# FRA_daughter_v1.net
KiCad netlist of a schematic drawn in EAGLE
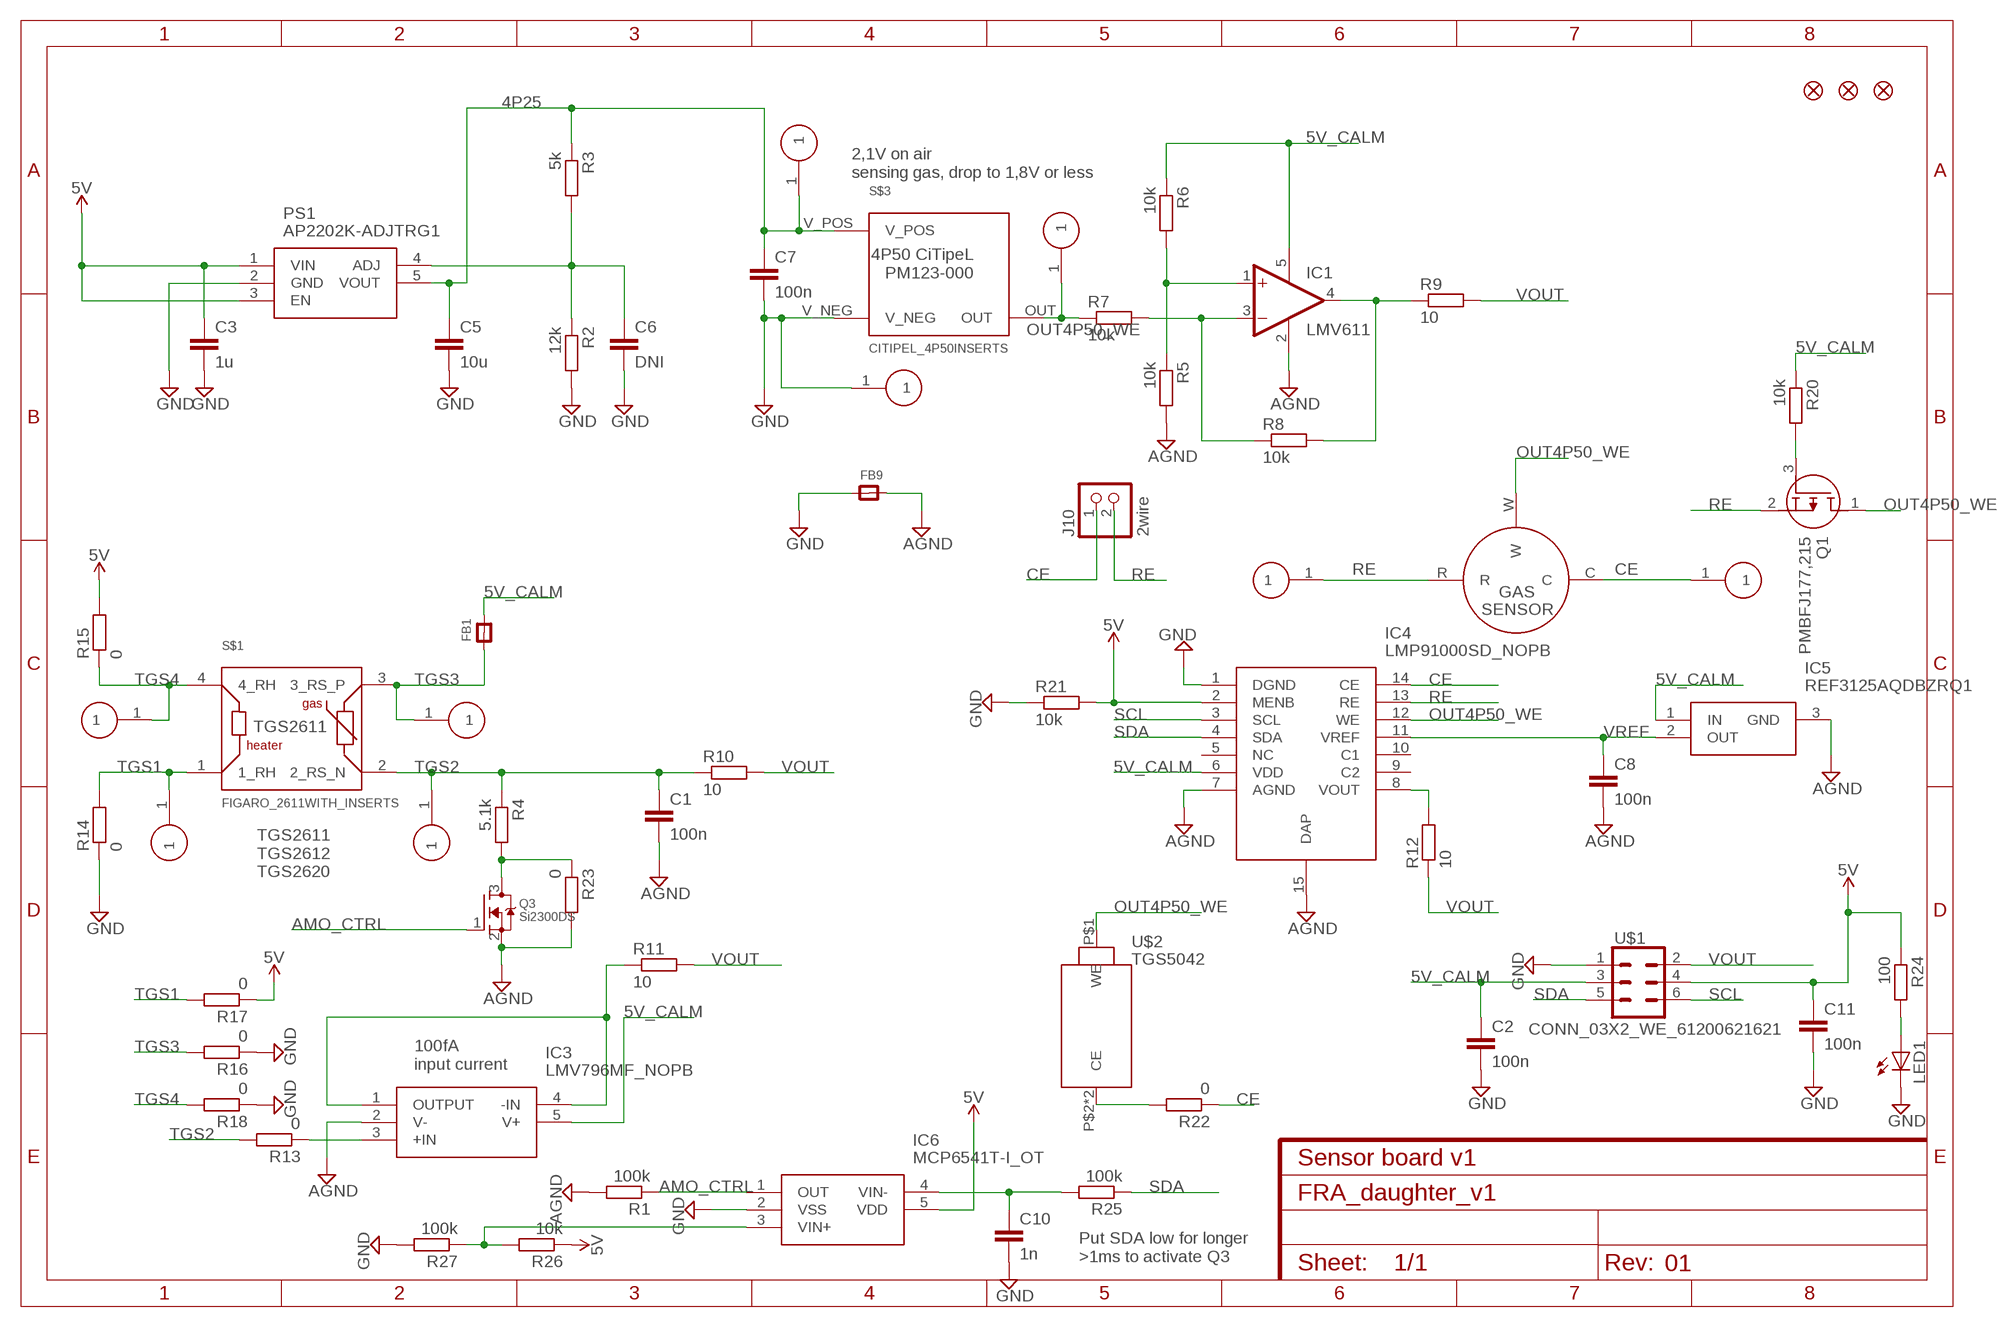
[diagram p0: schematic, sheet 1]

(export (version "E")
  (design (tool "Eeschema 10.0.6"))
  (components
    (comp (ref "C1")
      (value "100n")
      (footprint "eagle-import:C0603K")
      (libsource (lib "eagle-import") (part "C-EUC0603K"))
    )
    (comp (ref "C2")
      (value "100n")
      (footprint "eagle-import:C0603K")
      (libsource (lib "eagle-import") (part "C-EUC0603K"))
    )
    (comp (ref "C3")
      (value "1u")
      (footprint "eagle-import:C0603K")
      (libsource (lib "eagle-import") (part "C-EUC0603K"))
    )
    (comp (ref "C5")
      (value "10u")
      (footprint "eagle-import:C0603K")
      (libsource (lib "eagle-import") (part "C-EUC0603K"))
    )
    (comp (ref "C6")
      (value "DNI")
      (footprint "eagle-import:C0603K")
      (libsource (lib "eagle-import") (part "C-EUC0603K"))
    )
    (comp (ref "C7")
      (value "100n")
      (footprint "eagle-import:C0603K")
      (libsource (lib "eagle-import") (part "C-EUC0603K"))
    )
    (comp (ref "C8")
      (value "100n")
      (footprint "eagle-import:C0603K")
      (libsource (lib "eagle-import") (part "C-EUC0603K"))
    )
    (comp (ref "C10")
      (value "1n")
      (footprint "eagle-import:C0603K")
      (libsource (lib "eagle-import") (part "C-EUC0603K"))
    )
    (comp (ref "C11")
      (value "100n")
      (footprint "eagle-import:C0603K")
      (libsource (lib "eagle-import") (part "C-EUC0603K"))
    )
    (comp (ref "FB1")
      (value "FERRITE")
      (footprint "eagle-import:0603")
      (fields (field (name "PARTNO") "BLM18PG121SN1D"))
      (libsource (lib "eagle-import") (part "FERRITE"))
    )
    (comp (ref "FB9")
      (value "FERRITE")
      (footprint "eagle-import:0603")
      (fields (field (name "PARTNO") "BLM18PG121SN1D"))
      (libsource (lib "eagle-import") (part "FERRITE"))
    )
    (comp (ref "FID1")
      (value "FIDUCIAL\"\"")
      (footprint "eagle-import:FIDUCIAL_1MM")
      (libsource (lib "eagle-import") (part "FIDUCIAL{dblquote}{dblquote}"))
    )
    (comp (ref "FID2")
      (value "FIDUCIAL\"\"")
      (footprint "eagle-import:FIDUCIAL_1MM")
      (libsource (lib "eagle-import") (part "FIDUCIAL{dblquote}{dblquote}"))
    )
    (comp (ref "FID4")
      (value "FIDUCIAL\"\"")
      (footprint "eagle-import:FIDUCIAL_1MM")
      (libsource (lib "eagle-import") (part "FIDUCIAL{dblquote}{dblquote}"))
    )
    (comp (ref "IC1")
      (value "LMV611")
      (footprint "eagle-import:SC70-5L")
      (libsource (lib "eagle-import") (part "OPA333DCK"))
    )
    (comp (ref "IC3")
      (value "LMV796MF_NOPB")
      (footprint "eagle-import:SOT95P280X145-5N")
      (fields
        (field (name "MANUFACTURER_PART_NUMBER") "LMV796MF/NOPB")
        (field (name "MOUSER_PART_NUMBER") "926-LMV796MF/NOPB")
      )
      (libsource (lib "eagle-import") (part "LMV796MF_NOPB"))
    )
    (comp (ref "IC4")
      (value "LMP91000SD_NOPB")
      (footprint "eagle-import:SON50P400X400X80-15N")
      (fields
        (field (name "MANUFACTURER_PART_NUMBER") "LMP91000SD/NOPB")
        (field (name "MOUSER_PART_NUMBER") "926-LMP91000SD/NOPB")
      )
      (libsource (lib "eagle-import") (part "LMP91000SD_NOPB"))
    )
    (comp (ref "IC5")
      (value "REF3125AQDBZRQ1")
      (footprint "eagle-import:SOT95P237X112-3N")
      (fields (field (name "MOUSER_PART_NUMBER") "595-REF3125AQDBZRQ1"))
      (libsource (lib "eagle-import") (part "REF3125AQDBZRQ1"))
    )
    (comp (ref "IC6")
      (value "MCP6541T-I_OT")
      (footprint "eagle-import:SOT95P270X145-5N")
      (fields
        (field (name "MANUFACTURER_PART_NUMBER") "MCP6541T-I/OT")
        (field (name "MOUSER_PART_NUMBER") "579-MCP6541T-I/OT")
      )
      (libsource (lib "eagle-import") (part "MCP6541T-I_OT"))
    )
    (comp (ref "J1")
      (value "INSERT_MM5_06691.5MM")
      (footprint "eagle-import:INSERT_1MM5_9372")
      (libsource (lib "eagle-import") (part "INSERT_MM5_06691.5MM"))
    )
    (comp (ref "J2")
      (value "TGS3")
      (footprint "eagle-import:INSERT_MM5_0669")
      (libsource (lib "eagle-import") (part "INSERT_MM5_0669"))
    )
    (comp (ref "J3")
      (value "TGS2")
      (footprint "eagle-import:INSERT_MM5_0669")
      (libsource (lib "eagle-import") (part "INSERT_MM5_0669"))
    )
    (comp (ref "J4")
      (value "TGS1")
      (footprint "eagle-import:INSERT_MM5_0669")
      (libsource (lib "eagle-import") (part "INSERT_MM5_0669"))
    )
    (comp (ref "J5")
      (value "TGS4")
      (footprint "eagle-import:INSERT_MM5_0669")
      (libsource (lib "eagle-import") (part "INSERT_MM5_0669"))
    )
    (comp (ref "J6")
      (value "INSERT_MM5_06691.5MM")
      (footprint "eagle-import:INSERT_1MM5_9372")
      (libsource (lib "eagle-import") (part "INSERT_MM5_06691.5MM"))
    )
    (comp (ref "J7")
      (value "INSERT_MM5_06691.5MM")
      (footprint "eagle-import:INSERT_1MM5_9372")
      (libsource (lib "eagle-import") (part "INSERT_MM5_06691.5MM"))
    )
    (comp (ref "J8")
      (value "INSERT_MM5_06691.5MM")
      (footprint "eagle-import:INSERT_1MM5_9372")
      (libsource (lib "eagle-import") (part "INSERT_MM5_06691.5MM"))
    )
    (comp (ref "J9")
      (value "INSERT_MM5_06691.5MM")
      (footprint "eagle-import:INSERT_1MM5_9372")
      (libsource (lib "eagle-import") (part "INSERT_MM5_06691.5MM"))
    )
    (comp (ref "J10")
      (value "2wire")
      (footprint "eagle-import:1X02")
      (fields (field (name "PARTNO") "TSW-102-07-G-S"))
      (libsource (lib "eagle-import") (part "PINHD-1X2"))
    )
    (comp (ref "LED1")
      (value "LEDCHIP-LED0603")
      (footprint "eagle-import:CHIP-LED0603")
      (libsource (lib "eagle-import") (part "LEDCHIP-LED0603"))
    )
    (comp (ref "PS1")
      (value "AP2202K-ADJTRG1")
      (footprint "eagle-import:SOT95P280X145-5N")
      (fields (field (name "MOUSER_PART_NUMBER") "621-AP2202K-ADJTRG1"))
      (libsource (lib "eagle-import") (part "AP2202K-ADJTRG1"))
    )
    (comp (ref "Q1")
      (value "PMBFJ177,215")
      (footprint "eagle-import:SOT95P230X110-3N")
      (fields (field (name "MOUSER_PART_NUMBER") "771-PMBFJ177-T/R"))
      (libsource (lib "eagle-import") (part "PMBFJ177,215"))
    )
    (comp (ref "Q3")
      (value "Si2300DS")
      (footprint "eagle-import:SOT23")
      (libsource (lib "eagle-import") (part "MOSFET-NREFLOW"))
    )
    (comp (ref "R1")
      (value "100k")
      (footprint "eagle-import:R0603")
      (libsource (lib "eagle-import") (part "R-EU_R0603"))
    )
    (comp (ref "R2")
      (value "12k")
      (footprint "eagle-import:R0603")
      (libsource (lib "eagle-import") (part "R-EU_R0603"))
    )
    (comp (ref "R3")
      (value "5k")
      (footprint "eagle-import:R0603")
      (libsource (lib "eagle-import") (part "R-EU_R0603"))
    )
    (comp (ref "R4")
      (value "5.1k")
      (footprint "eagle-import:R0603")
      (libsource (lib "eagle-import") (part "R-EU_R0603"))
    )
    (comp (ref "R5")
      (value "10k")
      (footprint "eagle-import:R0603")
      (libsource (lib "eagle-import") (part "R-EU_R0603"))
    )
    (comp (ref "R6")
      (value "10k")
      (footprint "eagle-import:R0603")
      (libsource (lib "eagle-import") (part "R-EU_R0603"))
    )
    (comp (ref "R7")
      (value "10k")
      (footprint "eagle-import:R0603")
      (libsource (lib "eagle-import") (part "R-EU_R0603"))
    )
    (comp (ref "R8")
      (value "10k")
      (footprint "eagle-import:R0603")
      (libsource (lib "eagle-import") (part "R-EU_R0603"))
    )
    (comp (ref "R9")
      (value "10")
      (footprint "eagle-import:R0603")
      (libsource (lib "eagle-import") (part "R-EU_R0603"))
    )
    (comp (ref "R10")
      (value "10")
      (footprint "eagle-import:R0603")
      (libsource (lib "eagle-import") (part "R-EU_R0603"))
    )
    (comp (ref "R11")
      (value "10")
      (footprint "eagle-import:R0603")
      (libsource (lib "eagle-import") (part "R-EU_R0603"))
    )
    (comp (ref "R12")
      (value "10")
      (footprint "eagle-import:R0603")
      (libsource (lib "eagle-import") (part "R-EU_R0603"))
    )
    (comp (ref "R13")
      (value "0")
      (footprint "eagle-import:R0603")
      (libsource (lib "eagle-import") (part "R-EU_R0603"))
    )
    (comp (ref "R14")
      (value "0")
      (footprint "eagle-import:R0603")
      (libsource (lib "eagle-import") (part "R-EU_R0603"))
    )
    (comp (ref "R15")
      (value "0")
      (footprint "eagle-import:R0603")
      (libsource (lib "eagle-import") (part "R-EU_R0603"))
    )
    (comp (ref "R16")
      (value "0")
      (footprint "eagle-import:R0603")
      (libsource (lib "eagle-import") (part "R-EU_R0603"))
    )
    (comp (ref "R17")
      (value "0")
      (footprint "eagle-import:R0603")
      (libsource (lib "eagle-import") (part "R-EU_R0603"))
    )
    (comp (ref "R18")
      (value "0")
      (footprint "eagle-import:R0603")
      (libsource (lib "eagle-import") (part "R-EU_R0603"))
    )
    (comp (ref "R20")
      (value "10k")
      (footprint "eagle-import:R0603")
      (libsource (lib "eagle-import") (part "R-EU_R0603"))
    )
    (comp (ref "R21")
      (value "10k")
      (footprint "eagle-import:R0603")
      (libsource (lib "eagle-import") (part "R-EU_R0603"))
    )
    (comp (ref "R22")
      (value "0")
      (footprint "eagle-import:R0603")
      (libsource (lib "eagle-import") (part "R-EU_R0603"))
    )
    (comp (ref "R23")
      (value "0")
      (footprint "eagle-import:R0603")
      (libsource (lib "eagle-import") (part "R-EU_R0603"))
    )
    (comp (ref "R24")
      (value "100")
      (footprint "eagle-import:R0603")
      (libsource (lib "eagle-import") (part "R-EU_R0603"))
    )
    (comp (ref "R25")
      (value "100k")
      (footprint "eagle-import:R0603")
      (libsource (lib "eagle-import") (part "R-EU_R0603"))
    )
    (comp (ref "R26")
      (value "10k")
      (footprint "eagle-import:R0603")
      (libsource (lib "eagle-import") (part "R-EU_R0603"))
    )
    (comp (ref "R27")
      (value "100k")
      (footprint "eagle-import:R0603")
      (libsource (lib "eagle-import") (part "R-EU_R0603"))
    )
    (comp (ref "S$1")
      (value "FIGARO_2611WITH_INSERTS")
      (footprint "eagle-import:TH4_TGS2611_INSERTS")
      (libsource (lib "eagle-import") (part "FIGARO_2611WITH_INSERTS"))
    )
    (comp (ref "S$3")
      (value "CITIPEL_4P50INSERTS")
      (footprint "eagle-import:TH3_4P50_INSERTS")
      (libsource (lib "eagle-import") (part "CITIPEL_4P50INSERTS"))
    )
    (comp (ref "U$1")
      (value "CONN_03X2_WE_61200621621")
      (footprint "eagle-import:WE_61200621621")
      (libsource (lib "eagle-import") (part "CONN_03X2_WE_61200621621"))
    )
    (comp (ref "U$2")
      (value "TGS5042")
      (footprint "eagle-import:TGS5042")
      (libsource (lib "eagle-import") (part "TGS5042"))
    )
    (comp (ref "X1")
      (value "3-ELECTRODE-GAS-SENSORINS")
      (footprint "eagle-import:3-ELECTRODE_INSETRS")
      (libsource (lib "eagle-import") (part "3-ELECTRODE-GAS-SENSORINS"))
    )
  )
  (nets
    (net (code "1") (name "/4P25") (class "Default")
      (node (ref "C5") (pin "1") (pinfunction "1_1") (pintype "passive"))
      (node (ref "C7") (pin "1") (pinfunction "1_1") (pintype "passive"))
      (node (ref "J6") (pin "1") (pinfunction "1_1") (pintype "bidirectional"))
      (node (ref "PS1") (pin "5") (pinfunction "VOUT_5") (pintype "power_in"))
      (node (ref "R3") (pin "1") (pinfunction "1_1") (pintype "passive"))
      (node (ref "S$3") (pin "V_POS") (pinfunction "V_POS_V_POS") (pintype "power_in"))
    )
    (net (code "2") (name "/5V_CALM") (class "Default")
      (node (ref "C2") (pin "1") (pinfunction "1_1") (pintype "passive"))
      (node (ref "FB1") (pin "2") (pinfunction "P$2_2") (pintype "passive"))
      (node (ref "IC1") (pin "5") (pinfunction "V+_5") (pintype "power_in"))
      (node (ref "IC3") (pin "5") (pinfunction "V+_5") (pintype "bidirectional"))
      (node (ref "IC4") (pin "6") (pinfunction "VDD_6") (pintype "power_in"))
      (node (ref "IC5") (pin "1") (pinfunction "IN_1") (pintype "bidirectional"))
      (node (ref "R20") (pin "1") (pinfunction "1_1") (pintype "passive"))
      (node (ref "R6") (pin "1") (pinfunction "1_1") (pintype "passive"))
      (node (ref "U$1") (pin "3") (pinfunction "3_3") (pintype "bidirectional"))
    )
    (net (code "3") (name "/AMO_CTRL") (class "Default")
      (node (ref "IC6") (pin "1") (pinfunction "OUT_1") (pintype "output"))
      (node (ref "Q3") (pin "1") (pinfunction "G_1") (pintype "bidirectional"))
      (node (ref "R1") (pin "1") (pinfunction "1_1") (pintype "passive"))
    )
    (net (code "4") (name "/CE") (class "Default")
      (node (ref "IC4") (pin "14") (pinfunction "CE_14") (pintype "input"))
      (node (ref "J10") (pin "1") (pinfunction "1_1") (pintype "passive"))
      (node (ref "J9") (pin "1") (pinfunction "1_1") (pintype "bidirectional"))
      (node (ref "R22") (pin "1") (pinfunction "1_1") (pintype "passive"))
      (node (ref "X1") (pin "C") (pinfunction "C_C") (pintype "bidirectional"))
    )
    (net (code "5") (name "/OUT4P50_WE") (class "Default")
      (node (ref "IC4") (pin "12") (pinfunction "WE_12") (pintype "input"))
      (node (ref "J7") (pin "1") (pinfunction "1_1") (pintype "bidirectional"))
      (node (ref "Q1") (pin "1") (pinfunction "D_1") (pintype "bidirectional"))
      (node (ref "R7") (pin "1") (pinfunction "1_1") (pintype "passive"))
      (node (ref "S$3") (pin "OUT") (pinfunction "OUT_OUT") (pintype "bidirectional"))
      (node (ref "U$2") (pin "P$1") (pinfunction "WE_P$1") (pintype "bidirectional"))
      (node (ref "X1") (pin "W") (pinfunction "W_W") (pintype "bidirectional"))
    )
    (net (code "6") (name "/RE") (class "Default")
      (node (ref "IC4") (pin "13") (pinfunction "RE_13") (pintype "input"))
      (node (ref "J10") (pin "2") (pinfunction "2_2") (pintype "passive"))
      (node (ref "J8") (pin "1") (pinfunction "1_1") (pintype "bidirectional"))
      (node (ref "Q1") (pin "2") (pinfunction "S_2") (pintype "bidirectional"))
      (node (ref "X1") (pin "R") (pinfunction "R_R") (pintype "bidirectional"))
    )
    (net (code "7") (name "/SCL") (class "Default")
      (node (ref "IC4") (pin "3") (pinfunction "SCL_3") (pintype "input"))
      (node (ref "U$1") (pin "6") (pinfunction "6_6") (pintype "bidirectional"))
    )
    (net (code "8") (name "/SDA") (class "Default")
      (node (ref "IC4") (pin "4") (pinfunction "SDA_4") (pintype "bidirectional"))
      (node (ref "R25") (pin "1") (pinfunction "1_1") (pintype "passive"))
      (node (ref "U$1") (pin "5") (pinfunction "5_5") (pintype "bidirectional"))
    )
    (net (code "9") (name "/TGS1") (class "Default")
      (node (ref "J4") (pin "1") (pinfunction "1_1") (pintype "bidirectional"))
      (node (ref "R14") (pin "2") (pinfunction "2_2") (pintype "passive"))
      (node (ref "R17") (pin "2") (pinfunction "2_2") (pintype "passive"))
      (node (ref "S$1") (pin "1") (pinfunction "1_RH_1") (pintype "bidirectional"))
    )
    (net (code "10") (name "/TGS2") (class "Default")
      (node (ref "C1") (pin "1") (pinfunction "1_1") (pintype "passive"))
      (node (ref "J3") (pin "1") (pinfunction "1_1") (pintype "bidirectional"))
      (node (ref "R10") (pin "1") (pinfunction "1_1") (pintype "passive"))
      (node (ref "R13") (pin "2") (pinfunction "2_2") (pintype "passive"))
      (node (ref "R4") (pin "1") (pinfunction "1_1") (pintype "passive"))
      (node (ref "S$1") (pin "2") (pinfunction "2_RS_N_2") (pintype "bidirectional"))
    )
    (net (code "11") (name "/TGS3") (class "Default")
      (node (ref "FB1") (pin "1") (pinfunction "P$1_1") (pintype "passive"))
      (node (ref "J2") (pin "1") (pinfunction "1_1") (pintype "bidirectional"))
      (node (ref "R16") (pin "2") (pinfunction "2_2") (pintype "passive"))
      (node (ref "S$1") (pin "3") (pinfunction "3_RS_P_3") (pintype "bidirectional"))
    )
    (net (code "12") (name "/TGS4") (class "Default")
      (node (ref "J5") (pin "1") (pinfunction "1_1") (pintype "bidirectional"))
      (node (ref "R15") (pin "1") (pinfunction "1_1") (pintype "passive"))
      (node (ref "R18") (pin "2") (pinfunction "2_2") (pintype "passive"))
      (node (ref "S$1") (pin "4") (pinfunction "4_RH_4") (pintype "bidirectional"))
    )
    (net (code "13") (name "/VOUT") (class "Default")
      (node (ref "R10") (pin "2") (pinfunction "2_2") (pintype "passive"))
      (node (ref "R11") (pin "2") (pinfunction "2_2") (pintype "passive"))
      (node (ref "R12") (pin "1") (pinfunction "1_1") (pintype "passive"))
      (node (ref "R9") (pin "2") (pinfunction "2_2") (pintype "passive"))
      (node (ref "U$1") (pin "2") (pinfunction "2_2") (pintype "bidirectional"))
    )
    (net (code "14") (name "/VREF") (class "Default")
      (node (ref "C8") (pin "1") (pinfunction "1_1") (pintype "passive"))
      (node (ref "IC4") (pin "11") (pinfunction "VREF_11") (pintype "input"))
      (node (ref "IC5") (pin "2") (pinfunction "OUT_2") (pintype "bidirectional"))
    )
    (net (code "15") (name "5V") (class "Default")
      (node (ref "C11") (pin "1") (pinfunction "1_1") (pintype "passive"))
      (node (ref "C3") (pin "1") (pinfunction "1_1") (pintype "passive"))
      (node (ref "IC4") (pin "2") (pinfunction "MENB_2") (pintype "input"))
      (node (ref "IC6") (pin "5") (pinfunction "VDD_5") (pintype "power_in"))
      (node (ref "PS1") (pin "1") (pinfunction "VIN_1") (pintype "power_in"))
      (node (ref "PS1") (pin "3") (pinfunction "EN_3") (pintype "input"))
      (node (ref "R15") (pin "2") (pinfunction "2_2") (pintype "passive"))
      (node (ref "R17") (pin "1") (pinfunction "1_1") (pintype "passive"))
      (node (ref "R21") (pin "2") (pinfunction "2_2") (pintype "passive"))
      (node (ref "R24") (pin "1") (pinfunction "1_1") (pintype "passive"))
      (node (ref "R26") (pin "1") (pinfunction "1_1") (pintype "passive"))
      (node (ref "U$1") (pin "4") (pinfunction "4_4") (pintype "bidirectional"))
    )
    (net (code "16") (name "AGND") (class "Default")
      (node (ref "C1") (pin "2") (pinfunction "2_2") (pintype "passive"))
      (node (ref "C8") (pin "2") (pinfunction "2_2") (pintype "passive"))
      (node (ref "FB9") (pin "2") (pinfunction "P$2_2") (pintype "passive"))
      (node (ref "IC1") (pin "2") (pinfunction "V-_2") (pintype "power_in"))
      (node (ref "IC3") (pin "2") (pinfunction "V-_2") (pintype "bidirectional"))
      (node (ref "IC4") (pin "15") (pinfunction "DAP_15") (pintype "power_in"))
      (node (ref "IC4") (pin "7") (pinfunction "AGND_7") (pintype "power_in"))
      (node (ref "IC5") (pin "3") (pinfunction "GND_3") (pintype "bidirectional"))
      (node (ref "Q3") (pin "2") (pinfunction "S_2") (pintype "bidirectional"))
      (node (ref "R1") (pin "2") (pinfunction "2_2") (pintype "passive"))
      (node (ref "R23") (pin "2") (pinfunction "2_2") (pintype "passive"))
      (node (ref "R5") (pin "2") (pinfunction "2_2") (pintype "passive"))
    )
    (net (code "17") (name "GND") (class "Default")
      (node (ref "C10") (pin "2") (pinfunction "2_2") (pintype "passive"))
      (node (ref "C11") (pin "2") (pinfunction "2_2") (pintype "passive"))
      (node (ref "C2") (pin "2") (pinfunction "2_2") (pintype "passive"))
      (node (ref "C3") (pin "2") (pinfunction "2_2") (pintype "passive"))
      (node (ref "C5") (pin "2") (pinfunction "2_2") (pintype "passive"))
      (node (ref "C6") (pin "2") (pinfunction "2_2") (pintype "passive"))
      (node (ref "C7") (pin "2") (pinfunction "2_2") (pintype "passive"))
      (node (ref "FB9") (pin "1") (pinfunction "P$1_1") (pintype "passive"))
      (node (ref "IC4") (pin "1") (pinfunction "DGND_1") (pintype "power_in"))
      (node (ref "IC6") (pin "2") (pinfunction "VSS_2") (pintype "power_in"))
      (node (ref "J1") (pin "1") (pinfunction "1_1") (pintype "bidirectional"))
      (node (ref "LED1") (pin "C") (pinfunction "C_C") (pintype "passive"))
      (node (ref "PS1") (pin "2") (pinfunction "GND_2") (pintype "power_in"))
      (node (ref "R14") (pin "1") (pinfunction "1_1") (pintype "passive"))
      (node (ref "R16") (pin "1") (pinfunction "1_1") (pintype "passive"))
      (node (ref "R18") (pin "1") (pinfunction "1_1") (pintype "passive"))
      (node (ref "R2") (pin "2") (pinfunction "2_2") (pintype "passive"))
      (node (ref "R21") (pin "1") (pinfunction "1_1") (pintype "passive"))
      (node (ref "R27") (pin "2") (pinfunction "2_2") (pintype "passive"))
      (node (ref "S$3") (pin "V_NEG") (pinfunction "V_NEG_V_NEG") (pintype "power_in"))
      (node (ref "U$1") (pin "1") (pinfunction "1_1") (pintype "bidirectional"))
    )
    (net (code "18") (name "Net-(IC1-+IN)") (class "Default")
      (node (ref "IC1") (pin "1") (pinfunction "+IN_1") (pintype "input"))
      (node (ref "R5") (pin "1") (pinfunction "1_1") (pintype "passive"))
      (node (ref "R6") (pin "2") (pinfunction "2_2") (pintype "passive"))
    )
    (net (code "19") (name "Net-(IC1--IN)") (class "Default")
      (node (ref "IC1") (pin "3") (pinfunction "-IN_3") (pintype "input"))
      (node (ref "R7") (pin "2") (pinfunction "2_2") (pintype "passive"))
      (node (ref "R8") (pin "1") (pinfunction "1_1") (pintype "passive"))
    )
    (net (code "20") (name "Net-(IC1-OUT)") (class "Default")
      (node (ref "IC1") (pin "4") (pinfunction "OUT_4") (pintype "output"))
      (node (ref "R8") (pin "2") (pinfunction "2_2") (pintype "passive"))
      (node (ref "R9") (pin "1") (pinfunction "1_1") (pintype "passive"))
    )
    (net (code "21") (name "Net-(IC3-+IN)") (class "Default")
      (node (ref "IC3") (pin "3") (pinfunction "+IN_3") (pintype "input"))
      (node (ref "R13") (pin "1") (pinfunction "1_1") (pintype "passive"))
    )
    (net (code "22") (name "Net-(IC3--IN)") (class "Default")
      (node (ref "IC3") (pin "1") (pinfunction "OUTPUT_1") (pintype "output"))
      (node (ref "IC3") (pin "4") (pinfunction "-IN_4") (pintype "input"))
      (node (ref "R11") (pin "1") (pinfunction "1_1") (pintype "passive"))
    )
    (net (code "23") (name "Net-(IC4-VOUT)") (class "Default")
      (node (ref "IC4") (pin "8") (pinfunction "VOUT_8") (pintype "output"))
      (node (ref "R12") (pin "2") (pinfunction "2_2") (pintype "passive"))
    )
    (net (code "24") (name "Net-(IC6-VIN+)") (class "Default")
      (node (ref "IC6") (pin "3") (pinfunction "VIN+_3") (pintype "input"))
      (node (ref "R26") (pin "2") (pinfunction "2_2") (pintype "passive"))
      (node (ref "R27") (pin "1") (pinfunction "1_1") (pintype "passive"))
    )
    (net (code "25") (name "Net-(IC6-VIN-)") (class "Default")
      (node (ref "C10") (pin "1") (pinfunction "1_1") (pintype "passive"))
      (node (ref "IC6") (pin "4") (pinfunction "VIN-_4") (pintype "input"))
      (node (ref "R25") (pin "2") (pinfunction "2_2") (pintype "passive"))
    )
    (net (code "26") (name "Net-(LED1-PadA)") (class "Default")
      (node (ref "LED1") (pin "A") (pinfunction "A_A") (pintype "passive"))
      (node (ref "R24") (pin "2") (pinfunction "2_2") (pintype "passive"))
    )
    (net (code "27") (name "Net-(PS1-ADJ)") (class "Default")
      (node (ref "C6") (pin "1") (pinfunction "1_1") (pintype "passive"))
      (node (ref "PS1") (pin "4") (pinfunction "ADJ_4") (pintype "bidirectional"))
      (node (ref "R2") (pin "1") (pinfunction "1_1") (pintype "passive"))
      (node (ref "R3") (pin "2") (pinfunction "2_2") (pintype "passive"))
    )
    (net (code "28") (name "Net-(Q1-G)") (class "Default")
      (node (ref "Q1") (pin "3") (pinfunction "G_3") (pintype "bidirectional"))
      (node (ref "R20") (pin "2") (pinfunction "2_2") (pintype "passive"))
    )
    (net (code "29") (name "Net-(Q3-D)") (class "Default")
      (node (ref "Q3") (pin "3") (pinfunction "D_3") (pintype "bidirectional"))
      (node (ref "R23") (pin "1") (pinfunction "1_1") (pintype "passive"))
      (node (ref "R4") (pin "2") (pinfunction "2_2") (pintype "passive"))
    )
    (net (code "30") (name "Net-(R22-Pad2)") (class "Default")
      (node (ref "R22") (pin "2") (pinfunction "2_2") (pintype "passive"))
      (node (ref "U$2") (pin "P$2") (pinfunction "CE_P$2") (pintype "bidirectional"))
      (node (ref "U$2") (pin "P$3") (pinfunction "CE_P$3") (pintype "bidirectional"))
    )
    (net (code "31") (name "unconnected-(IC4-C1-Pad10)") (class "Default")
      (node (ref "IC4") (pin "10") (pinfunction "C1_10") (pintype "bidirectional"))
    )
    (net (code "32") (name "unconnected-(IC4-C2-Pad9)") (class "Default")
      (node (ref "IC4") (pin "9") (pinfunction "C2_9") (pintype "bidirectional"))
    )
    (net (code "33") (name "unconnected-(IC4-NC-Pad5)") (class "Default")
      (node (ref "IC4") (pin "5") (pinfunction "NC_5") (pintype "no_connect"))
    )
  )
)
